# DRV8876_Breakout.net
KiCad netlist of a schematic drawn in EAGLE
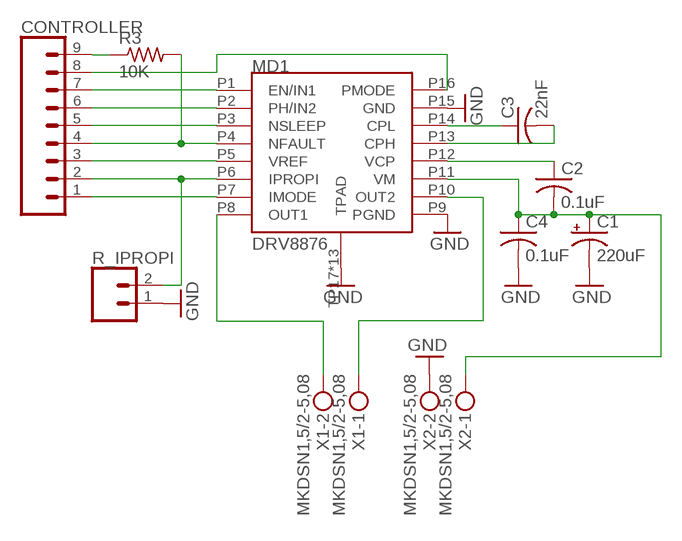
[diagram p0: schematic, sheet 1]

(export (version "E")
  (design (tool "Eeschema 10.0.6"))
  (components
    (comp (ref "C1")
      (value "220uF")
      (footprint "eagle-import:E3,5-8")
      (libsource (lib "eagle-import") (part "CPOL-USE3.5-8"))
    )
    (comp (ref "C2")
      (value "0.1uF")
      (footprint "eagle-import:C0805")
      (libsource (lib "eagle-import") (part "C-USC0805"))
    )
    (comp (ref "C3")
      (value "22nF")
      (footprint "eagle-import:C0805")
      (libsource (lib "eagle-import") (part "C-USC0805"))
    )
    (comp (ref "C4")
      (value "0.1uF")
      (footprint "eagle-import:C0805")
      (libsource (lib "eagle-import") (part "C-USC0805"))
    )
    (comp (ref "CONTROLLER")
      (value "CONN_09NO_SILK")
      (footprint "eagle-import:1X09_NO_SILK")
      (libsource (lib "eagle-import") (part "CONN_09NO_SILK"))
    )
    (comp (ref "MD1")
      (value "DRV8876")
      (footprint "eagle-import:DRV8876")
      (libsource (lib "eagle-import") (part "DRV8876"))
    )
    (comp (ref "R3")
      (value "10K")
      (footprint "eagle-import:R0805")
      (libsource (lib "eagle-import") (part "R-US_R0805"))
    )
    (comp (ref "R_IPROPI")
      (value "CONN_021X02_NO_SILK")
      (footprint "eagle-import:1X02_NO_SILK")
      (libsource (lib "eagle-import") (part "CONN_021X02_NO_SILK"))
    )
    (comp (ref "X1")
      (value "MKDSN1,5/2-5,08")
      (footprint "eagle-import:MKDSN1,5_2-5,08")
      (libsource (lib "eagle-import") (part "MKDSN1,5/2-5,08"))
    )
    (comp (ref "X2")
      (value "MKDSN1,5/2-5,08")
      (footprint "eagle-import:MKDSN1,5_2-5,08")
      (libsource (lib "eagle-import") (part "MKDSN1,5/2-5,08"))
    )
  )
  (nets
    (net (code "1") (name "GND") (class "Default")
      (node (ref "C1") (pin "-") (pinfunction "-_-") (pintype "passive"))
      (node (ref "C4") (pin "2") (pinfunction "2_2") (pintype "passive"))
      (node (ref "MD1") (pin "P15") (pinfunction "GND_P15") (pintype "bidirectional"))
      (node (ref "MD1") (pin "P9") (pinfunction "PGND_P9") (pintype "bidirectional"))
      (node (ref "MD1") (pin "TP17") (pinfunction "TPAD_TP17") (pintype "bidirectional"))
      (node (ref "MD1") (pin "TV18") (pinfunction "TPAD_TV18") (pintype "bidirectional"))
      (node (ref "MD1") (pin "TV19") (pinfunction "TPAD_TV19") (pintype "bidirectional"))
      (node (ref "MD1") (pin "TV20") (pinfunction "TPAD_TV20") (pintype "bidirectional"))
      (node (ref "MD1") (pin "TV21") (pinfunction "TPAD_TV21") (pintype "bidirectional"))
      (node (ref "MD1") (pin "TV22") (pinfunction "TPAD_TV22") (pintype "bidirectional"))
      (node (ref "MD1") (pin "TV23") (pinfunction "TPAD_TV23") (pintype "bidirectional"))
      (node (ref "MD1") (pin "TV24") (pinfunction "TPAD_TV24") (pintype "bidirectional"))
      (node (ref "MD1") (pin "TV25") (pinfunction "TPAD_TV25") (pintype "bidirectional"))
      (node (ref "MD1") (pin "TV26") (pinfunction "TPAD_TV26") (pintype "bidirectional"))
      (node (ref "MD1") (pin "TV27") (pinfunction "TPAD_TV27") (pintype "bidirectional"))
      (node (ref "MD1") (pin "TV28") (pinfunction "TPAD_TV28") (pintype "bidirectional"))
      (node (ref "MD1") (pin "TV29") (pinfunction "TPAD_TV29") (pintype "bidirectional"))
      (node (ref "R_IPROPI") (pin "1") (pinfunction "1_1") (pintype "passive"))
      (node (ref "X2") (pin "2") (pinfunction "KL_2") (pintype "passive"))
    )
    (net (code "2") (name "Net-(CONTROLLER-Pad9)") (class "Default")
      (node (ref "CONTROLLER") (pin "9") (pinfunction "9_9") (pintype "passive"))
      (node (ref "R3") (pin "1") (pinfunction "1_1") (pintype "passive"))
    )
    (net (code "3") (name "Net-(MD1-CPH)") (class "Default")
      (node (ref "C3") (pin "2") (pinfunction "2_2") (pintype "passive"))
      (node (ref "MD1") (pin "P13") (pinfunction "CPH_P13") (pintype "bidirectional"))
    )
    (net (code "4") (name "Net-(MD1-CPL)") (class "Default")
      (node (ref "C3") (pin "1") (pinfunction "1_1") (pintype "passive"))
      (node (ref "MD1") (pin "P14") (pinfunction "CPL_P14") (pintype "bidirectional"))
    )
    (net (code "5") (name "Net-(MD1-EN{slash}IN1)") (class "Default")
      (node (ref "CONTROLLER") (pin "7") (pinfunction "7_7") (pintype "passive"))
      (node (ref "MD1") (pin "P1") (pinfunction "EN/IN1_P1") (pintype "bidirectional"))
    )
    (net (code "6") (name "Net-(MD1-IMODE)") (class "Default")
      (node (ref "CONTROLLER") (pin "1") (pinfunction "1_1") (pintype "passive"))
      (node (ref "MD1") (pin "P7") (pinfunction "IMODE_P7") (pintype "bidirectional"))
    )
    (net (code "7") (name "Net-(MD1-IPROPI)") (class "Default")
      (node (ref "CONTROLLER") (pin "2") (pinfunction "2_2") (pintype "passive"))
      (node (ref "MD1") (pin "P6") (pinfunction "IPROPI_P6") (pintype "bidirectional"))
      (node (ref "R_IPROPI") (pin "2") (pinfunction "2_2") (pintype "passive"))
    )
    (net (code "8") (name "Net-(MD1-NFAULT)") (class "Default")
      (node (ref "CONTROLLER") (pin "4") (pinfunction "4_4") (pintype "passive"))
      (node (ref "MD1") (pin "P4") (pinfunction "NFAULT_P4") (pintype "bidirectional"))
      (node (ref "R3") (pin "2") (pinfunction "2_2") (pintype "passive"))
    )
    (net (code "9") (name "Net-(MD1-NSLEEP)") (class "Default")
      (node (ref "CONTROLLER") (pin "5") (pinfunction "5_5") (pintype "passive"))
      (node (ref "MD1") (pin "P3") (pinfunction "NSLEEP_P3") (pintype "bidirectional"))
    )
    (net (code "10") (name "Net-(MD1-OUT1)") (class "Default")
      (node (ref "MD1") (pin "P8") (pinfunction "OUT1_P8") (pintype "bidirectional"))
      (node (ref "X1") (pin "2") (pinfunction "KL_2") (pintype "passive"))
    )
    (net (code "11") (name "Net-(MD1-OUT2)") (class "Default")
      (node (ref "MD1") (pin "P10") (pinfunction "OUT2_P10") (pintype "bidirectional"))
      (node (ref "X1") (pin "1") (pinfunction "KL_1") (pintype "passive"))
    )
    (net (code "12") (name "Net-(MD1-PH{slash}IN2)") (class "Default")
      (node (ref "CONTROLLER") (pin "6") (pinfunction "6_6") (pintype "passive"))
      (node (ref "MD1") (pin "P2") (pinfunction "PH/IN2_P2") (pintype "bidirectional"))
    )
    (net (code "13") (name "Net-(MD1-PMODE)") (class "Default")
      (node (ref "CONTROLLER") (pin "8") (pinfunction "8_8") (pintype "passive"))
      (node (ref "MD1") (pin "P16") (pinfunction "PMODE_P16") (pintype "bidirectional"))
    )
    (net (code "14") (name "Net-(MD1-VCP)") (class "Default")
      (node (ref "C2") (pin "1") (pinfunction "1_1") (pintype "passive"))
      (node (ref "MD1") (pin "P12") (pinfunction "VCP_P12") (pintype "bidirectional"))
    )
    (net (code "15") (name "Net-(MD1-VM)") (class "Default")
      (node (ref "C1") (pin "+") (pinfunction "+_+") (pintype "passive"))
      (node (ref "C2") (pin "2") (pinfunction "2_2") (pintype "passive"))
      (node (ref "C4") (pin "1") (pinfunction "1_1") (pintype "passive"))
      (node (ref "MD1") (pin "P11") (pinfunction "VM_P11") (pintype "bidirectional"))
      (node (ref "X2") (pin "1") (pinfunction "KL_1") (pintype "passive"))
    )
    (net (code "16") (name "Net-(MD1-VREF)") (class "Default")
      (node (ref "CONTROLLER") (pin "3") (pinfunction "3_3") (pintype "passive"))
      (node (ref "MD1") (pin "P5") (pinfunction "VREF_P5") (pintype "bidirectional"))
    )
  )
)
